# proto4-left.net
KiCad netlist of a schematic drawn in EAGLE
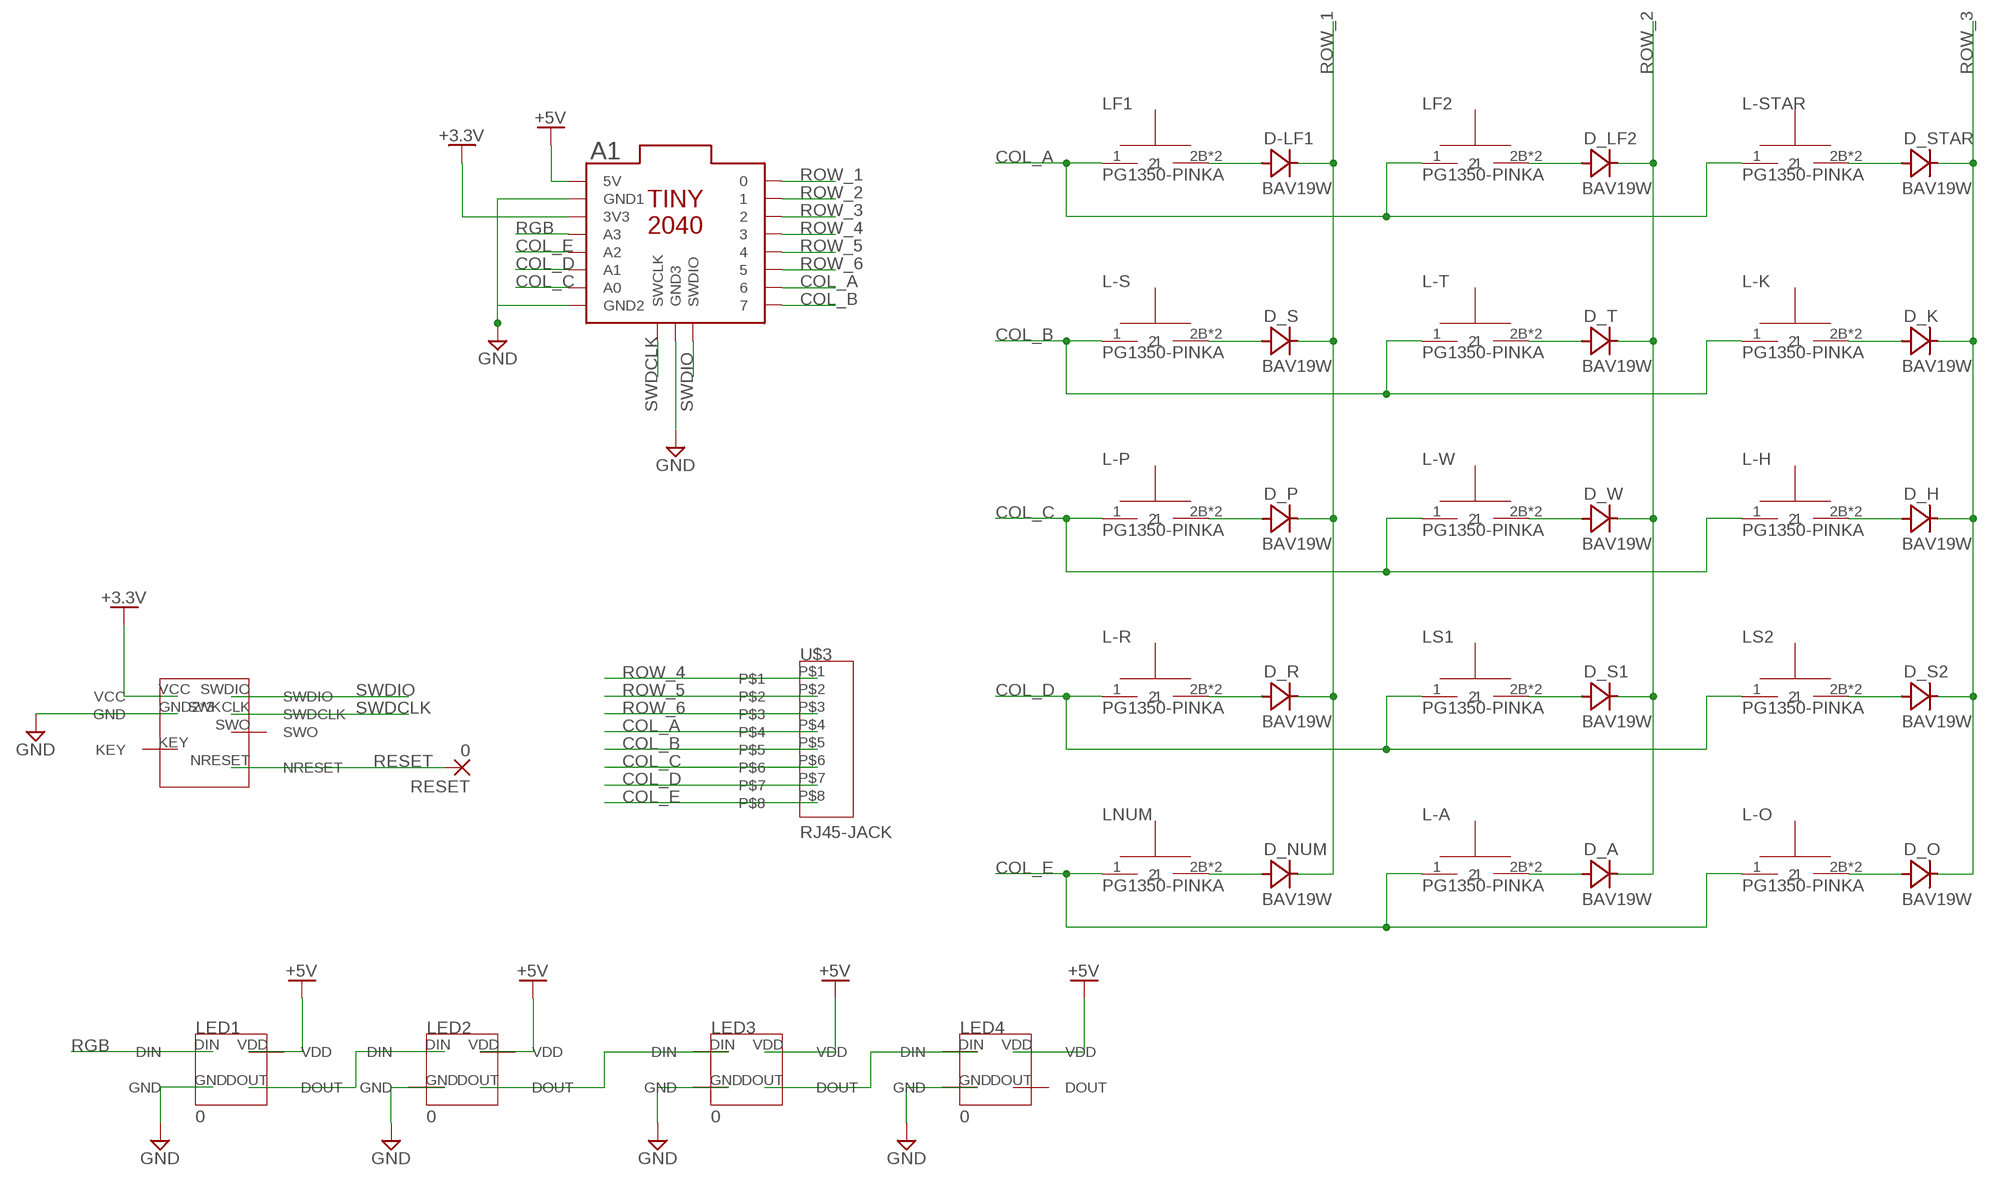
[diagram p0: schematic, sheet 1]

(export (version "E")
  (design (tool "Eeschema 10.0.6"))
  (components
    (comp (ref "A1")
      (value "TINY2040")
      (footprint "eagle-import:TINY2040")
      (libsource (lib "eagle-import") (part "TINY2040"))
    )
    (comp (ref "D-LF1")
      (value "BAV19W")
      (footprint "eagle-import:SOD123")
      (libsource (lib "eagle-import") (part "BAV19W"))
    )
    (comp (ref "D_A")
      (value "BAV19W")
      (footprint "eagle-import:SOD123")
      (libsource (lib "eagle-import") (part "BAV19W"))
    )
    (comp (ref "D_H")
      (value "BAV19W")
      (footprint "eagle-import:SOD123")
      (libsource (lib "eagle-import") (part "BAV19W"))
    )
    (comp (ref "D_K")
      (value "BAV19W")
      (footprint "eagle-import:SOD123")
      (libsource (lib "eagle-import") (part "BAV19W"))
    )
    (comp (ref "D_LF2")
      (value "BAV19W")
      (footprint "eagle-import:SOD123")
      (libsource (lib "eagle-import") (part "BAV19W"))
    )
    (comp (ref "D_NUM")
      (value "BAV19W")
      (footprint "eagle-import:SOD123")
      (libsource (lib "eagle-import") (part "BAV19W"))
    )
    (comp (ref "D_O")
      (value "BAV19W")
      (footprint "eagle-import:SOD123")
      (libsource (lib "eagle-import") (part "BAV19W"))
    )
    (comp (ref "D_P")
      (value "BAV19W")
      (footprint "eagle-import:SOD123")
      (libsource (lib "eagle-import") (part "BAV19W"))
    )
    (comp (ref "D_R")
      (value "BAV19W")
      (footprint "eagle-import:SOD123")
      (libsource (lib "eagle-import") (part "BAV19W"))
    )
    (comp (ref "D_S")
      (value "BAV19W")
      (footprint "eagle-import:SOD123")
      (libsource (lib "eagle-import") (part "BAV19W"))
    )
    (comp (ref "D_S1")
      (value "BAV19W")
      (footprint "eagle-import:SOD123")
      (libsource (lib "eagle-import") (part "BAV19W"))
    )
    (comp (ref "D_S2")
      (value "BAV19W")
      (footprint "eagle-import:SOD123")
      (libsource (lib "eagle-import") (part "BAV19W"))
    )
    (comp (ref "D_STAR")
      (value "BAV19W")
      (footprint "eagle-import:SOD123")
      (libsource (lib "eagle-import") (part "BAV19W"))
    )
    (comp (ref "D_T")
      (value "BAV19W")
      (footprint "eagle-import:SOD123")
      (libsource (lib "eagle-import") (part "BAV19W"))
    )
    (comp (ref "D_W")
      (value "BAV19W")
      (footprint "eagle-import:SOD123")
      (libsource (lib "eagle-import") (part "BAV19W"))
    )
    (comp (ref "L-A")
      (value "PG1350-PINKA")
      (footprint "eagle-import:PG1350")
      (libsource (lib "eagle-import") (part "PG1350-PINKA"))
    )
    (comp (ref "L-H")
      (value "PG1350-PINKA")
      (footprint "eagle-import:PG1350")
      (libsource (lib "eagle-import") (part "PG1350-PINKA"))
    )
    (comp (ref "L-K")
      (value "PG1350-PINKA")
      (footprint "eagle-import:PG1350")
      (libsource (lib "eagle-import") (part "PG1350-PINKA"))
    )
    (comp (ref "L-O")
      (value "PG1350-PINKA")
      (footprint "eagle-import:PG1350")
      (libsource (lib "eagle-import") (part "PG1350-PINKA"))
    )
    (comp (ref "L-P")
      (value "PG1350-PINKA")
      (footprint "eagle-import:PG1350")
      (libsource (lib "eagle-import") (part "PG1350-PINKA"))
    )
    (comp (ref "L-R")
      (value "PG1350-PINKA")
      (footprint "eagle-import:PG1350")
      (libsource (lib "eagle-import") (part "PG1350-PINKA"))
    )
    (comp (ref "L-S")
      (value "PG1350-PINKA")
      (footprint "eagle-import:PG1350")
      (libsource (lib "eagle-import") (part "PG1350-PINKA"))
    )
    (comp (ref "L-STAR")
      (value "PG1350-PINKA")
      (footprint "eagle-import:PG1350")
      (libsource (lib "eagle-import") (part "PG1350-PINKA"))
    )
    (comp (ref "L-T")
      (value "PG1350-PINKA")
      (footprint "eagle-import:PG1350")
      (libsource (lib "eagle-import") (part "PG1350-PINKA"))
    )
    (comp (ref "L-W")
      (value "PG1350-PINKA")
      (footprint "eagle-import:PG1350")
      (libsource (lib "eagle-import") (part "PG1350-PINKA"))
    )
    (comp (ref "LED1")
      (value "0")
      (footprint "eagle-import:SK6812-MINI-HS")
      (libsource (lib "eagle-import") (part "SK6812-3535"))
    )
    (comp (ref "LED2")
      (value "0")
      (footprint "eagle-import:SK6812-MINI-HS")
      (libsource (lib "eagle-import") (part "SK6812-3535"))
    )
    (comp (ref "LED3")
      (value "0")
      (footprint "eagle-import:SK6812-MINI-HS")
      (libsource (lib "eagle-import") (part "SK6812-3535"))
    )
    (comp (ref "LED4")
      (value "0")
      (footprint "eagle-import:SK6812-MINI-HS")
      (libsource (lib "eagle-import") (part "SK6812-3535"))
    )
    (comp (ref "LF1")
      (value "PG1350-PINKA")
      (footprint "eagle-import:PG1350")
      (libsource (lib "eagle-import") (part "PG1350-PINKA"))
    )
    (comp (ref "LF2")
      (value "PG1350-PINKA")
      (footprint "eagle-import:PG1350")
      (libsource (lib "eagle-import") (part "PG1350-PINKA"))
    )
    (comp (ref "LNUM")
      (value "PG1350-PINKA")
      (footprint "eagle-import:PG1350")
      (libsource (lib "eagle-import") (part "PG1350-PINKA"))
    )
    (comp (ref "LS1")
      (value "PG1350-PINKA")
      (footprint "eagle-import:PG1350")
      (libsource (lib "eagle-import") (part "PG1350-PINKA"))
    )
    (comp (ref "LS2")
      (value "PG1350-PINKA")
      (footprint "eagle-import:PG1350")
      (libsource (lib "eagle-import") (part "PG1350-PINKA"))
    )
    (comp (ref "RESET")
      (value "0")
      (footprint "eagle-import:SMD1,27-2,54")
      (libsource (lib "eagle-import") (part "SMD2"))
    )
    (comp (ref "U$2")
      (value "CORTEX-M0")
      (footprint "eagle-import:CORTEX-M10")
      (libsource (lib "eagle-import") (part "CORTEX-M0"))
    )
    (comp (ref "U$3")
      (value "RJ45-JACK")
      (footprint "eagle-import:C-BMJ-0051-RJ45")
      (libsource (lib "eagle-import") (part "RJ45-JACK"))
    )
  )
  (nets
    (net (code "1") (name "+3.3V") (class "Default")
      (node (ref "A1") (pin "3V3") (pinfunction "3V3_3V3") (pintype "bidirectional"))
      (node (ref "U$2") (pin "VCC") (pinfunction "VCC_VCC") (pintype "bidirectional"))
    )
    (net (code "2") (name "+5V") (class "Default")
      (node (ref "A1") (pin "5V") (pinfunction "5V_5V") (pintype "bidirectional"))
      (node (ref "LED1") (pin "VDD") (pinfunction "VDD_VDD") (pintype "power_in"))
      (node (ref "LED2") (pin "VDD") (pinfunction "VDD_VDD") (pintype "power_in"))
      (node (ref "LED3") (pin "VDD") (pinfunction "VDD_VDD") (pintype "power_in"))
      (node (ref "LED4") (pin "VDD") (pinfunction "VDD_VDD") (pintype "power_in"))
    )
    (net (code "3") (name "/COL_A") (class "Default")
      (node (ref "A1") (pin "6") (pinfunction "6_6") (pintype "bidirectional"))
      (node (ref "L-STAR") (pin "1") (pinfunction "1_1") (pintype "passive"))
      (node (ref "LF1") (pin "1") (pinfunction "1_1") (pintype "passive"))
      (node (ref "LF2") (pin "1") (pinfunction "1_1") (pintype "passive"))
      (node (ref "U$3") (pin "P$4") (pinfunction "P$4_P$4") (pintype "bidirectional"))
    )
    (net (code "4") (name "/COL_B") (class "Default")
      (node (ref "A1") (pin "7") (pinfunction "7_7") (pintype "bidirectional"))
      (node (ref "L-K") (pin "1") (pinfunction "1_1") (pintype "passive"))
      (node (ref "L-S") (pin "1") (pinfunction "1_1") (pintype "passive"))
      (node (ref "L-T") (pin "1") (pinfunction "1_1") (pintype "passive"))
      (node (ref "U$3") (pin "P$5") (pinfunction "P$5_P$5") (pintype "bidirectional"))
    )
    (net (code "5") (name "/COL_C") (class "Default")
      (node (ref "A1") (pin "A0") (pinfunction "A0_A0") (pintype "bidirectional"))
      (node (ref "L-H") (pin "1") (pinfunction "1_1") (pintype "passive"))
      (node (ref "L-P") (pin "1") (pinfunction "1_1") (pintype "passive"))
      (node (ref "L-W") (pin "1") (pinfunction "1_1") (pintype "passive"))
      (node (ref "U$3") (pin "P$6") (pinfunction "P$6_P$6") (pintype "bidirectional"))
    )
    (net (code "6") (name "/COL_D") (class "Default")
      (node (ref "A1") (pin "A1") (pinfunction "A1_A1") (pintype "bidirectional"))
      (node (ref "L-R") (pin "1") (pinfunction "1_1") (pintype "passive"))
      (node (ref "LS1") (pin "1") (pinfunction "1_1") (pintype "passive"))
      (node (ref "LS2") (pin "1") (pinfunction "1_1") (pintype "passive"))
      (node (ref "U$3") (pin "P$7") (pinfunction "P$7_P$7") (pintype "bidirectional"))
    )
    (net (code "7") (name "/COL_E") (class "Default")
      (node (ref "A1") (pin "A2") (pinfunction "A2_A2") (pintype "bidirectional"))
      (node (ref "L-A") (pin "1") (pinfunction "1_1") (pintype "passive"))
      (node (ref "L-O") (pin "1") (pinfunction "1_1") (pintype "passive"))
      (node (ref "LNUM") (pin "1") (pinfunction "1_1") (pintype "passive"))
      (node (ref "U$3") (pin "P$8") (pinfunction "P$8_P$8") (pintype "bidirectional"))
    )
    (net (code "8") (name "/RESET") (class "Default")
      (node (ref "RESET") (pin "1") (pinfunction "P_1") (pintype "passive"))
      (node (ref "U$2") (pin "NRESET") (pinfunction "NRESET_NRESET") (pintype "bidirectional"))
    )
    (net (code "9") (name "/RGB") (class "Default")
      (node (ref "A1") (pin "A3") (pinfunction "A3_A3") (pintype "bidirectional"))
      (node (ref "LED1") (pin "DIN") (pinfunction "DIN_DIN") (pintype "input"))
    )
    (net (code "10") (name "/ROW_1") (class "Default")
      (node (ref "A1") (pin "0") (pinfunction "0_0") (pintype "bidirectional"))
      (node (ref "D-LF1") (pin "C") (pinfunction "C_C") (pintype "passive"))
      (node (ref "D_NUM") (pin "C") (pinfunction "C_C") (pintype "passive"))
      (node (ref "D_P") (pin "C") (pinfunction "C_C") (pintype "passive"))
      (node (ref "D_R") (pin "C") (pinfunction "C_C") (pintype "passive"))
      (node (ref "D_S") (pin "C") (pinfunction "C_C") (pintype "passive"))
    )
    (net (code "11") (name "/ROW_2") (class "Default")
      (node (ref "A1") (pin "1") (pinfunction "1_1") (pintype "bidirectional"))
      (node (ref "D_A") (pin "C") (pinfunction "C_C") (pintype "passive"))
      (node (ref "D_LF2") (pin "C") (pinfunction "C_C") (pintype "passive"))
      (node (ref "D_S1") (pin "C") (pinfunction "C_C") (pintype "passive"))
      (node (ref "D_T") (pin "C") (pinfunction "C_C") (pintype "passive"))
      (node (ref "D_W") (pin "C") (pinfunction "C_C") (pintype "passive"))
    )
    (net (code "12") (name "/ROW_3") (class "Default")
      (node (ref "A1") (pin "2") (pinfunction "2_2") (pintype "bidirectional"))
      (node (ref "D_H") (pin "C") (pinfunction "C_C") (pintype "passive"))
      (node (ref "D_K") (pin "C") (pinfunction "C_C") (pintype "passive"))
      (node (ref "D_O") (pin "C") (pinfunction "C_C") (pintype "passive"))
      (node (ref "D_S2") (pin "C") (pinfunction "C_C") (pintype "passive"))
      (node (ref "D_STAR") (pin "C") (pinfunction "C_C") (pintype "passive"))
    )
    (net (code "13") (name "/ROW_4") (class "Default")
      (node (ref "A1") (pin "3") (pinfunction "3_3") (pintype "bidirectional"))
      (node (ref "U$3") (pin "P$1") (pinfunction "P$1_P$1") (pintype "bidirectional"))
    )
    (net (code "14") (name "/ROW_5") (class "Default")
      (node (ref "A1") (pin "4") (pinfunction "4_4") (pintype "bidirectional"))
      (node (ref "U$3") (pin "P$2") (pinfunction "P$2_P$2") (pintype "bidirectional"))
    )
    (net (code "15") (name "/ROW_6") (class "Default")
      (node (ref "A1") (pin "5") (pinfunction "5_5") (pintype "bidirectional"))
      (node (ref "U$3") (pin "P$3") (pinfunction "P$3_P$3") (pintype "bidirectional"))
    )
    (net (code "16") (name "/SWDCLK") (class "Default")
      (node (ref "A1") (pin "SWCLK") (pinfunction "SWCLK_SWCLK") (pintype "bidirectional"))
      (node (ref "U$2") (pin "SWKCLK") (pinfunction "SWDCLK_SWKCLK") (pintype "bidirectional"))
    )
    (net (code "17") (name "/SWDIO") (class "Default")
      (node (ref "A1") (pin "SWDIO") (pinfunction "SWDIO_SWDIO") (pintype "bidirectional"))
      (node (ref "U$2") (pin "SWDIO") (pinfunction "SWDIO_SWDIO") (pintype "bidirectional"))
    )
    (net (code "18") (name "GND") (class "Default")
      (node (ref "A1") (pin "GND1") (pinfunction "GND1_GND1") (pintype "bidirectional"))
      (node (ref "A1") (pin "GND2") (pinfunction "GND2_GND2") (pintype "bidirectional"))
      (node (ref "A1") (pin "GND3") (pinfunction "GND3_GND3") (pintype "bidirectional"))
      (node (ref "LED1") (pin "GND") (pinfunction "GND_GND") (pintype "power_in"))
      (node (ref "LED2") (pin "GND") (pinfunction "GND_GND") (pintype "power_in"))
      (node (ref "LED3") (pin "GND") (pinfunction "GND_GND") (pintype "power_in"))
      (node (ref "LED4") (pin "GND") (pinfunction "GND_GND") (pintype "power_in"))
      (node (ref "U$2") (pin "GND2") (pinfunction "GND_GND2") (pintype "bidirectional"))
      (node (ref "U$2") (pin "GND3") (pinfunction "GND_GND3") (pintype "bidirectional"))
      (node (ref "U$2") (pin "GNDDETECT") (pinfunction "GND_GNDDETECT") (pintype "bidirectional"))
    )
    (net (code "19") (name "Net-(D-LF1-PadA)") (class "Default")
      (node (ref "D-LF1") (pin "A") (pinfunction "A_A") (pintype "passive"))
      (node (ref "LF1") (pin "2B") (pinfunction "2_2B") (pintype "passive"))
      (node (ref "LF1") (pin "2T") (pinfunction "2_2T") (pintype "passive"))
    )
    (net (code "20") (name "Net-(D_A-PadA)") (class "Default")
      (node (ref "D_A") (pin "A") (pinfunction "A_A") (pintype "passive"))
      (node (ref "L-A") (pin "2B") (pinfunction "2_2B") (pintype "passive"))
      (node (ref "L-A") (pin "2T") (pinfunction "2_2T") (pintype "passive"))
    )
    (net (code "21") (name "Net-(D_H-PadA)") (class "Default")
      (node (ref "D_H") (pin "A") (pinfunction "A_A") (pintype "passive"))
      (node (ref "L-H") (pin "2B") (pinfunction "2_2B") (pintype "passive"))
      (node (ref "L-H") (pin "2T") (pinfunction "2_2T") (pintype "passive"))
    )
    (net (code "22") (name "Net-(D_K-PadA)") (class "Default")
      (node (ref "D_K") (pin "A") (pinfunction "A_A") (pintype "passive"))
      (node (ref "L-K") (pin "2B") (pinfunction "2_2B") (pintype "passive"))
      (node (ref "L-K") (pin "2T") (pinfunction "2_2T") (pintype "passive"))
    )
    (net (code "23") (name "Net-(D_LF2-PadA)") (class "Default")
      (node (ref "D_LF2") (pin "A") (pinfunction "A_A") (pintype "passive"))
      (node (ref "LF2") (pin "2B") (pinfunction "2_2B") (pintype "passive"))
      (node (ref "LF2") (pin "2T") (pinfunction "2_2T") (pintype "passive"))
    )
    (net (code "24") (name "Net-(D_NUM-PadA)") (class "Default")
      (node (ref "D_NUM") (pin "A") (pinfunction "A_A") (pintype "passive"))
      (node (ref "LNUM") (pin "2B") (pinfunction "2_2B") (pintype "passive"))
      (node (ref "LNUM") (pin "2T") (pinfunction "2_2T") (pintype "passive"))
    )
    (net (code "25") (name "Net-(D_O-PadA)") (class "Default")
      (node (ref "D_O") (pin "A") (pinfunction "A_A") (pintype "passive"))
      (node (ref "L-O") (pin "2B") (pinfunction "2_2B") (pintype "passive"))
      (node (ref "L-O") (pin "2T") (pinfunction "2_2T") (pintype "passive"))
    )
    (net (code "26") (name "Net-(D_P-PadA)") (class "Default")
      (node (ref "D_P") (pin "A") (pinfunction "A_A") (pintype "passive"))
      (node (ref "L-P") (pin "2B") (pinfunction "2_2B") (pintype "passive"))
      (node (ref "L-P") (pin "2T") (pinfunction "2_2T") (pintype "passive"))
    )
    (net (code "27") (name "Net-(D_R-PadA)") (class "Default")
      (node (ref "D_R") (pin "A") (pinfunction "A_A") (pintype "passive"))
      (node (ref "L-R") (pin "2B") (pinfunction "2_2B") (pintype "passive"))
      (node (ref "L-R") (pin "2T") (pinfunction "2_2T") (pintype "passive"))
    )
    (net (code "28") (name "Net-(D_S-PadA)") (class "Default")
      (node (ref "D_S") (pin "A") (pinfunction "A_A") (pintype "passive"))
      (node (ref "L-S") (pin "2B") (pinfunction "2_2B") (pintype "passive"))
      (node (ref "L-S") (pin "2T") (pinfunction "2_2T") (pintype "passive"))
    )
    (net (code "29") (name "Net-(D_S1-PadA)") (class "Default")
      (node (ref "D_S1") (pin "A") (pinfunction "A_A") (pintype "passive"))
      (node (ref "LS1") (pin "2B") (pinfunction "2_2B") (pintype "passive"))
      (node (ref "LS1") (pin "2T") (pinfunction "2_2T") (pintype "passive"))
    )
    (net (code "30") (name "Net-(D_S2-PadA)") (class "Default")
      (node (ref "D_S2") (pin "A") (pinfunction "A_A") (pintype "passive"))
      (node (ref "LS2") (pin "2B") (pinfunction "2_2B") (pintype "passive"))
      (node (ref "LS2") (pin "2T") (pinfunction "2_2T") (pintype "passive"))
    )
    (net (code "31") (name "Net-(D_STAR-PadA)") (class "Default")
      (node (ref "D_STAR") (pin "A") (pinfunction "A_A") (pintype "passive"))
      (node (ref "L-STAR") (pin "2B") (pinfunction "2_2B") (pintype "passive"))
      (node (ref "L-STAR") (pin "2T") (pinfunction "2_2T") (pintype "passive"))
    )
    (net (code "32") (name "Net-(D_T-PadA)") (class "Default")
      (node (ref "D_T") (pin "A") (pinfunction "A_A") (pintype "passive"))
      (node (ref "L-T") (pin "2B") (pinfunction "2_2B") (pintype "passive"))
      (node (ref "L-T") (pin "2T") (pinfunction "2_2T") (pintype "passive"))
    )
    (net (code "33") (name "Net-(D_W-PadA)") (class "Default")
      (node (ref "D_W") (pin "A") (pinfunction "A_A") (pintype "passive"))
      (node (ref "L-W") (pin "2B") (pinfunction "2_2B") (pintype "passive"))
      (node (ref "L-W") (pin "2T") (pinfunction "2_2T") (pintype "passive"))
    )
    (net (code "34") (name "Net-(LED1-PadDOUT)") (class "Default")
      (node (ref "LED1") (pin "DOUT") (pinfunction "DOUT_DOUT") (pintype "output"))
      (node (ref "LED2") (pin "DIN") (pinfunction "DIN_DIN") (pintype "input"))
    )
    (net (code "35") (name "Net-(LED2-PadDOUT)") (class "Default")
      (node (ref "LED2") (pin "DOUT") (pinfunction "DOUT_DOUT") (pintype "output"))
      (node (ref "LED3") (pin "DIN") (pinfunction "DIN_DIN") (pintype "input"))
    )
    (net (code "36") (name "Net-(LED3-PadDOUT)") (class "Default")
      (node (ref "LED3") (pin "DOUT") (pinfunction "DOUT_DOUT") (pintype "output"))
      (node (ref "LED4") (pin "DIN") (pinfunction "DIN_DIN") (pintype "input"))
    )
    (net (code "37") (name "unconnected-(LED4-PadDOUT)") (class "Default")
      (node (ref "LED4") (pin "DOUT") (pinfunction "DOUT_DOUT") (pintype "output"))
    )
    (net (code "38") (name "unconnected-(U$2-PadKEY)") (class "Default")
      (node (ref "U$2") (pin "KEY") (pinfunction "KEY_KEY") (pintype "bidirectional"))
    )
    (net (code "39") (name "unconnected-(U$2-PadSWO)") (class "Default")
      (node (ref "U$2") (pin "SWO") (pinfunction "SWO_SWO") (pintype "bidirectional"))
    )
  )
)
